# top.net
KiCad netlist of a schematic drawn in Altium Designer
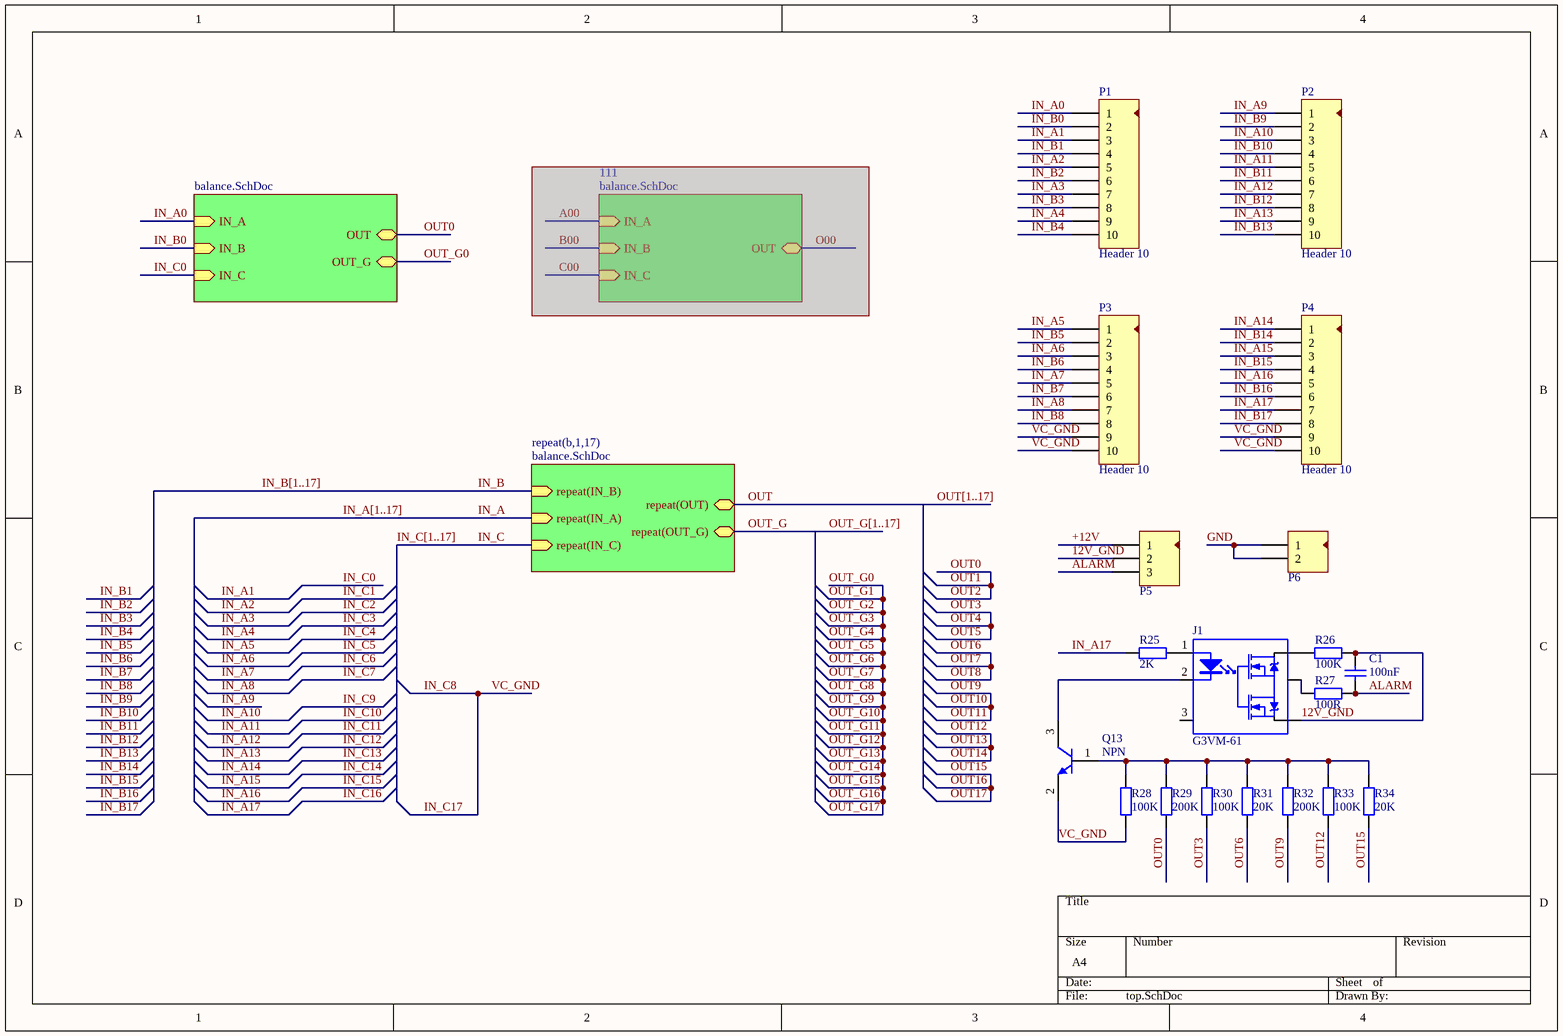
[diagram p0: top.SchDoc]

(export (version "E")
  (design (tool "Eeschema 10.0.6"))
  (components
    (comp (ref "C1")
      (value "100nF")
      (footprint "C-0603")
      (description "贴片瓷片电容")
      (fields (field (name "Comment") "Cap-S") (field (name "PUBLISHER") "Altium Limited"))
      (libsource (lib "Fszhang") (part "Cap-S"))
    )
    (comp (ref "J1")
      (value "G3VM-61")
      (footprint "DIP-6")
      (description "固态继电器")
      (libsource (lib "Fszhang") (part "G3VM-61"))
    )
    (comp (ref "P1")
      (value "Header 10")
      (footprint "HDR10X1-2.54")
      (description "接插件")
      (fields (field (name "PUBLISHER") "Altium Limited"))
      (libsource (lib "HDR_Fszhang") (part "Header 10"))
    )
    (comp (ref "P2")
      (value "Header 10")
      (footprint "HDR10X1-2.54")
      (description "接插件")
      (fields (field (name "PUBLISHER") "Altium Limited"))
      (libsource (lib "HDR_Fszhang") (part "Header 10"))
    )
    (comp (ref "P3")
      (value "Header 10")
      (footprint "HDR10X1-2.54")
      (description "接插件")
      (fields (field (name "PUBLISHER") "Altium Limited"))
      (libsource (lib "HDR_Fszhang") (part "Header 10"))
    )
    (comp (ref "P4")
      (value "Header 10")
      (footprint "HDR10X1-2.54")
      (description "接插件")
      (fields (field (name "PUBLISHER") "Altium Limited"))
      (libsource (lib "HDR_Fszhang") (part "Header 10"))
    )
    (comp (ref "P5")
      (value "Header 3")
      (footprint "HDR3X1-2.54")
      (description "接插件")
      (fields (field (name "PUBLISHER") "Altium Limited"))
      (libsource (lib "HDR_Fszhang") (part "Header 3"))
    )
    (comp (ref "P6")
      (value "Header 2")
      (footprint "HDR2X1-2.54")
      (description "接插件")
      (fields (field (name "PUBLISHER") "Altium Limited"))
      (libsource (lib "HDR_Fszhang") (part "Header 2"))
    )
    (comp (ref "Q13")
      (value "NPN")
      (footprint "SOT23-3")
      (description "贴片三极管")
      (fields (field (name "PUBLISHER") "Altium Limited"))
      (libsource (lib "Fszhang") (part "NPN1"))
    )
    (comp (ref "R25")
      (value "2K")
      (footprint "0603-1")
      (description "贴片电阻")
      (fields (field (name "Comment") "Res1") (field (name "PUBLISHER") "Altium Limited"))
      (libsource (lib "") (part "Res1_1"))
    )
    (comp (ref "R26")
      (value "100K")
      (footprint "0603-1")
      (description "贴片电阻")
      (fields (field (name "Comment") "Res1") (field (name "PUBLISHER") "Altium Limited"))
      (libsource (lib "") (part "Res1_1"))
    )
    (comp (ref "R27")
      (value "100R")
      (footprint "0603-1")
      (description "贴片电阻")
      (fields (field (name "Comment") "Res1") (field (name "PUBLISHER") "Altium Limited"))
      (libsource (lib "") (part "Res1_1"))
    )
    (comp (ref "R28")
      (value "100K")
      (footprint "0603-1")
      (description "贴片电阻")
      (fields (field (name "Comment") "Res1") (field (name "PUBLISHER") "Altium Limited"))
      (libsource (lib "Fszhang") (part "Res1"))
    )
    (comp (ref "R29")
      (value "200K")
      (footprint "0603-1")
      (description "贴片电阻")
      (fields (field (name "Comment") "Res1") (field (name "PUBLISHER") "Altium Limited"))
      (libsource (lib "Fszhang") (part "Res1"))
    )
    (comp (ref "R30")
      (value "100K")
      (footprint "0603-1")
      (description "贴片电阻")
      (fields (field (name "Comment") "Res1") (field (name "PUBLISHER") "Altium Limited"))
      (libsource (lib "Fszhang") (part "Res1"))
    )
    (comp (ref "R31")
      (value "20K")
      (footprint "0603-1")
      (description "贴片电阻")
      (fields (field (name "Comment") "Res1") (field (name "PUBLISHER") "Altium Limited"))
      (libsource (lib "Fszhang") (part "Res1"))
    )
    (comp (ref "R32")
      (value "200K")
      (footprint "0603-1")
      (description "贴片电阻")
      (fields (field (name "Comment") "Res1") (field (name "PUBLISHER") "Altium Limited"))
      (libsource (lib "Fszhang") (part "Res1"))
    )
    (comp (ref "R33")
      (value "100K")
      (footprint "0603-1")
      (description "贴片电阻")
      (fields (field (name "Comment") "Res1") (field (name "PUBLISHER") "Altium Limited"))
      (libsource (lib "Fszhang") (part "Res1"))
    )
    (comp (ref "R34")
      (value "20K")
      (footprint "0603-1")
      (description "贴片电阻")
      (fields (field (name "Comment") "Res1") (field (name "PUBLISHER") "Altium Limited"))
      (libsource (lib "Fszhang") (part "Res1"))
    )
  )
  (nets
    (net (code "1") (name "/+12V") (class "Default")
      (node (ref "P5") (pin "1") (pinfunction "1_1") (pintype "passive"))
    )
    (net (code "2") (name "/12V_GND") (class "Default")
      (node (ref "C1") (pin "2") (pinfunction "2_2") (pintype "passive"))
      (node (ref "J1") (pin "4") (pinfunction "4_4") (pintype "passive"))
      (node (ref "P5") (pin "2") (pinfunction "2_2") (pintype "passive"))
      (node (ref "R26") (pin "2") (pinfunction "2_2") (pintype "passive"))
    )
    (net (code "4") (name "/ALARM") (class "Default")
      (node (ref "C1") (pin "1") (pinfunction "1_1") (pintype "passive"))
      (node (ref "P5") (pin "3") (pinfunction "3_3") (pintype "passive"))
      (node (ref "R27") (pin "2") (pinfunction "2_2") (pintype "passive"))
    )
    (net (code "7") (name "/GND") (class "Default")
      (node (ref "P6") (pin "1") (pinfunction "1_1") (pintype "passive"))
      (node (ref "P6") (pin "2") (pinfunction "2_2") (pintype "passive"))
    )
    (net (code "9") (name "/IN_A0") (class "Default")
      (node (ref "P1") (pin "1") (pinfunction "1_1") (pintype "passive"))
    )
    (net (code "10") (name "/IN_A1") (class "Default")
      (node (ref "P1") (pin "3") (pinfunction "3_3") (pintype "passive"))
    )
    (net (code "11") (name "/IN_A9") (class "Default")
      (node (ref "P2") (pin "1") (pinfunction "1_1") (pintype "passive"))
    )
    (net (code "14") (name "/IN_B0") (class "Default")
      (node (ref "P1") (pin "2") (pinfunction "2_2") (pintype "passive"))
    )
    (net (code "15") (name "/IN_B1") (class "Default")
      (node (ref "P1") (pin "4") (pinfunction "4_4") (pintype "passive"))
    )
    (net (code "16") (name "/IN_B2") (class "Default")
      (node (ref "P1") (pin "6") (pinfunction "6_6") (pintype "passive"))
    )
    (net (code "17") (name "/IN_B3") (class "Default")
      (node (ref "P1") (pin "8") (pinfunction "8_8") (pintype "passive"))
    )
    (net (code "18") (name "/IN_B4") (class "Default")
      (node (ref "P1") (pin "10") (pinfunction "10_10") (pintype "passive"))
    )
    (net (code "19") (name "/IN_B5") (class "Default")
      (node (ref "P3") (pin "2") (pinfunction "2_2") (pintype "passive"))
    )
    (net (code "20") (name "/IN_B6") (class "Default")
      (node (ref "P3") (pin "4") (pinfunction "4_4") (pintype "passive"))
    )
    (net (code "21") (name "/IN_B7") (class "Default")
      (node (ref "P3") (pin "6") (pinfunction "6_6") (pintype "passive"))
    )
    (net (code "22") (name "/IN_B8") (class "Default")
      (node (ref "P3") (pin "8") (pinfunction "8_8") (pintype "passive"))
    )
    (net (code "23") (name "/IN_B9") (class "Default")
      (node (ref "P2") (pin "2") (pinfunction "2_2") (pintype "passive"))
    )
    (net (code "24") (name "/IN_B10") (class "Default")
      (node (ref "P2") (pin "4") (pinfunction "4_4") (pintype "passive"))
    )
    (net (code "25") (name "/IN_B11") (class "Default")
      (node (ref "P2") (pin "6") (pinfunction "6_6") (pintype "passive"))
    )
    (net (code "26") (name "/IN_B12") (class "Default")
      (node (ref "P2") (pin "8") (pinfunction "8_8") (pintype "passive"))
    )
    (net (code "27") (name "/IN_B13") (class "Default")
      (node (ref "P2") (pin "10") (pinfunction "10_10") (pintype "passive"))
    )
    (net (code "28") (name "/IN_B14") (class "Default")
      (node (ref "P4") (pin "2") (pinfunction "2_2") (pintype "passive"))
    )
    (net (code "29") (name "/IN_B15") (class "Default")
      (node (ref "P4") (pin "4") (pinfunction "4_4") (pintype "passive"))
    )
    (net (code "30") (name "/IN_B16") (class "Default")
      (node (ref "P4") (pin "6") (pinfunction "6_6") (pintype "passive"))
    )
    (net (code "31") (name "/IN_B17") (class "Default")
      (node (ref "P4") (pin "8") (pinfunction "8_8") (pintype "passive"))
    )
    (net (code "34") (name "/IN_C1") (class "Default")
      (node (ref "P1") (pin "5") (pinfunction "5_5") (pintype "passive"))
    )
    (net (code "35") (name "/IN_C2") (class "Default")
      (node (ref "P1") (pin "7") (pinfunction "7_7") (pintype "passive"))
    )
    (net (code "36") (name "/IN_C3") (class "Default")
      (node (ref "P1") (pin "9") (pinfunction "9_9") (pintype "passive"))
    )
    (net (code "37") (name "/IN_C4") (class "Default")
      (node (ref "P3") (pin "1") (pinfunction "1_1") (pintype "passive"))
    )
    (net (code "38") (name "/IN_C5") (class "Default")
      (node (ref "P3") (pin "3") (pinfunction "3_3") (pintype "passive"))
    )
    (net (code "39") (name "/IN_C6") (class "Default")
      (node (ref "P3") (pin "5") (pinfunction "5_5") (pintype "passive"))
    )
    (net (code "40") (name "/IN_C7") (class "Default")
      (node (ref "P3") (pin "7") (pinfunction "7_7") (pintype "passive"))
    )
    (net (code "41") (name "/IN_C8") (class "Default")
      (node (ref "P3") (pin "10") (pinfunction "10_10") (pintype "passive"))
      (node (ref "P3") (pin "9") (pinfunction "9_9") (pintype "passive"))
      (node (ref "P4") (pin "10") (pinfunction "10_10") (pintype "passive"))
      (node (ref "P4") (pin "9") (pinfunction "9_9") (pintype "passive"))
      (node (ref "Q13") (pin "2") (pinfunction "E_2") (pintype "passive"))
      (node (ref "R28") (pin "1") (pinfunction "1_1") (pintype "passive"))
    )
    (net (code "42") (name "/IN_C9") (class "Default")
      (node (ref "P2") (pin "3") (pinfunction "3_3") (pintype "passive"))
    )
    (net (code "43") (name "/IN_C10") (class "Default")
      (node (ref "P2") (pin "5") (pinfunction "5_5") (pintype "passive"))
    )
    (net (code "44") (name "/IN_C11") (class "Default")
      (node (ref "P2") (pin "7") (pinfunction "7_7") (pintype "passive"))
    )
    (net (code "45") (name "/IN_C12") (class "Default")
      (node (ref "P2") (pin "9") (pinfunction "9_9") (pintype "passive"))
    )
    (net (code "46") (name "/IN_C13") (class "Default")
      (node (ref "P4") (pin "1") (pinfunction "1_1") (pintype "passive"))
    )
    (net (code "47") (name "/IN_C14") (class "Default")
      (node (ref "P4") (pin "3") (pinfunction "3_3") (pintype "passive"))
    )
    (net (code "48") (name "/IN_C15") (class "Default")
      (node (ref "P4") (pin "5") (pinfunction "5_5") (pintype "passive"))
    )
    (net (code "49") (name "/IN_C16") (class "Default")
      (node (ref "P4") (pin "7") (pinfunction "7_7") (pintype "passive"))
      (node (ref "R25") (pin "1") (pinfunction "1_1") (pintype "passive"))
    )
    (net (code "53") (name "/OUT2") (class "Default")
      (node (ref "R29") (pin "1") (pinfunction "1_1") (pintype "passive"))
    )
    (net (code "54") (name "/OUT5") (class "Default")
      (node (ref "R30") (pin "1") (pinfunction "1_1") (pintype "passive"))
    )
    (net (code "55") (name "/OUT8") (class "Default")
      (node (ref "R31") (pin "1") (pinfunction "1_1") (pintype "passive"))
    )
    (net (code "56") (name "/OUT9") (class "Default")
      (node (ref "R32") (pin "1") (pinfunction "1_1") (pintype "passive"))
    )
    (net (code "57") (name "/OUT14") (class "Default")
      (node (ref "R33") (pin "1") (pinfunction "1_1") (pintype "passive"))
    )
    (net (code "58") (name "/OUT17") (class "Default")
      (node (ref "R34") (pin "1") (pinfunction "1_1") (pintype "passive"))
    )
    (net (code "63") (name "Net-(J1-A)") (class "Default")
      (node (ref "J1") (pin "1") (pinfunction "A_1") (pintype "passive"))
      (node (ref "R25") (pin "2") (pinfunction "2_2") (pintype "passive"))
    )
    (net (code "64") (name "Net-(J1-K)") (class "Default")
      (node (ref "J1") (pin "2") (pinfunction "K_2") (pintype "passive"))
      (node (ref "Q13") (pin "3") (pinfunction "C_3") (pintype "passive"))
    )
    (net (code "65") (name "Net-(J1-Pad5)") (class "Default")
      (node (ref "J1") (pin "5") (pinfunction "5_5") (pintype "passive"))
      (node (ref "R27") (pin "1") (pinfunction "1_1") (pintype "passive"))
    )
    (net (code "66") (name "Net-(J1-Pad6)") (class "Default")
      (node (ref "J1") (pin "6") (pinfunction "6_6") (pintype "passive"))
      (node (ref "R26") (pin "1") (pinfunction "1_1") (pintype "passive"))
    )
    (net (code "67") (name "Net-(Q13-B)") (class "Default")
      (node (ref "Q13") (pin "1") (pinfunction "B_1") (pintype "passive"))
      (node (ref "R28") (pin "2") (pinfunction "2_2") (pintype "passive"))
      (node (ref "R29") (pin "2") (pinfunction "2_2") (pintype "passive"))
      (node (ref "R30") (pin "2") (pinfunction "2_2") (pintype "passive"))
      (node (ref "R31") (pin "2") (pinfunction "2_2") (pintype "passive"))
      (node (ref "R32") (pin "2") (pinfunction "2_2") (pintype "passive"))
      (node (ref "R33") (pin "2") (pinfunction "2_2") (pintype "passive"))
      (node (ref "R34") (pin "2") (pinfunction "2_2") (pintype "passive"))
    )
    (net (code "68") (name "unconnected-(J1-Pad3)") (class "Default")
      (node (ref "J1") (pin "3") (pinfunction "3_3") (pintype "passive"))
    )
  )
)
